# bqZUM_Scan_Shield.net
KiCad netlist of a schematic drawn in Altium Designer
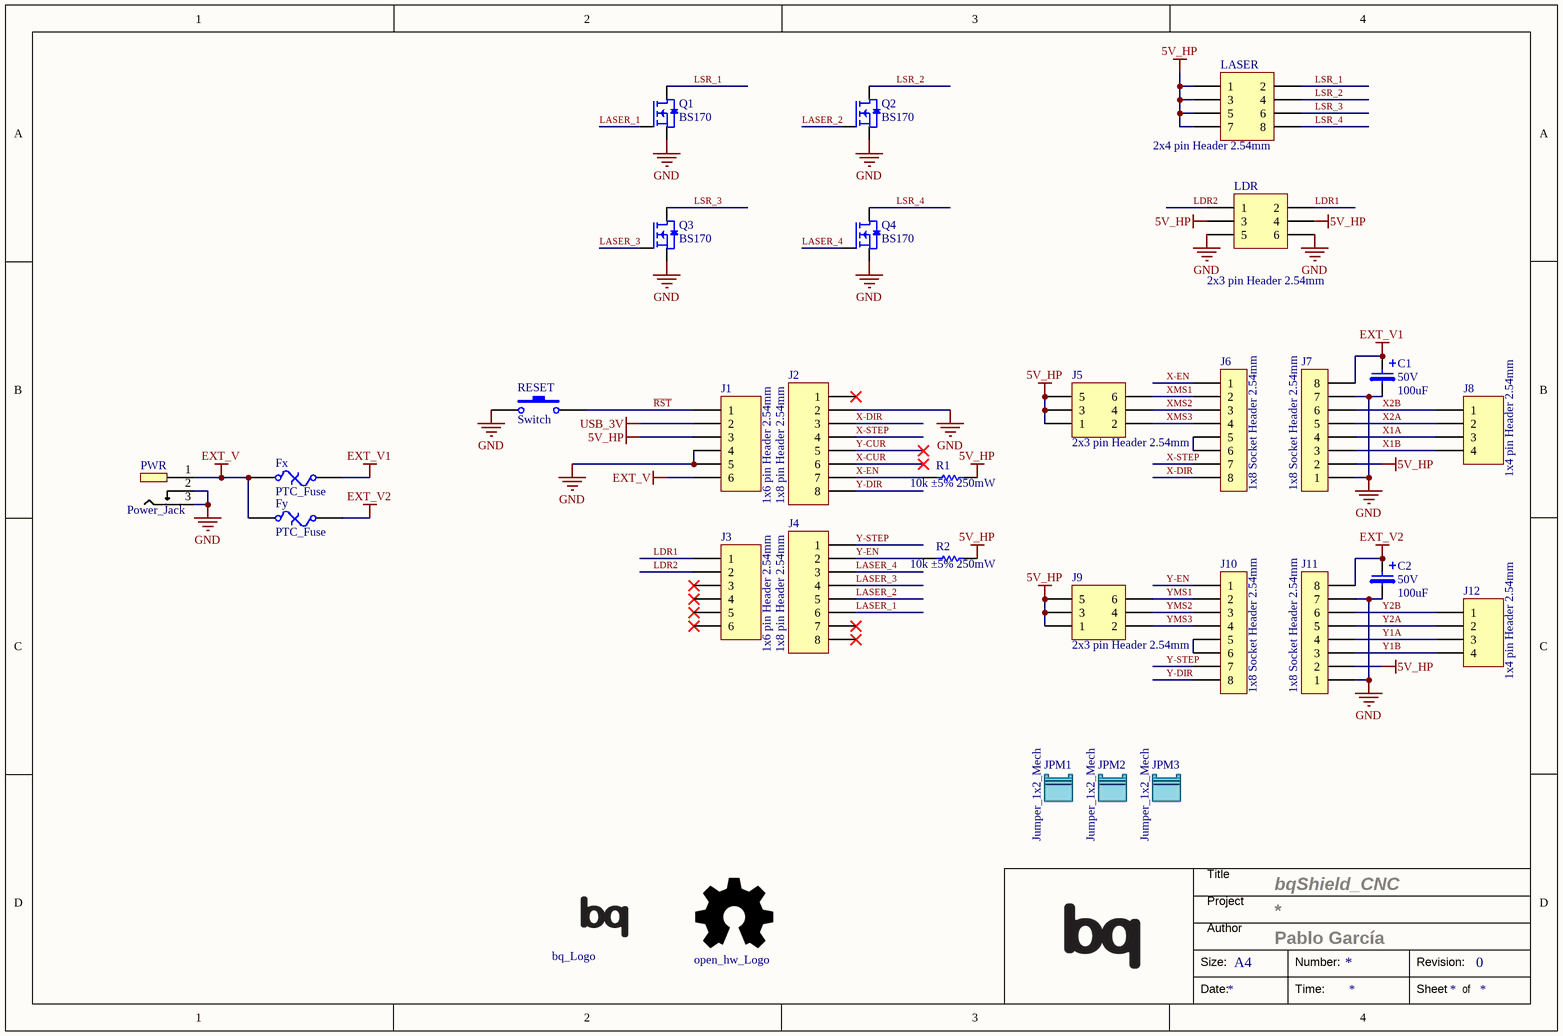
[diagram p0: bqZUM_Scan_Shield.SchDoc]

(export (version "E")
  (design (tool "Eeschema 10.0.6"))
  (components
    (comp (ref "C1")
      (value "Electrolytic")
      (footprint "Body_8-Height_11.5-Space_3,5_Folded")
      (description "Capacitor Electrolytic")
      (fields
        (field (name "VOLTAGE") "50V")
        (field (name "CAPACITANCE") "100uF")
        (field (name "PART NUMBER") "CAP_EL_100uF_50V")
        (field (name "MANUFACTURER") "Nichicon")
      )
      (libsource (lib "Pasives_Electrolytic_THT") (part "Electrolytic"))
    )
    (comp (ref "C2")
      (value "Electrolytic")
      (footprint "Body_8-Height_11.5-Space_3,5_Folded")
      (description "Capacitor Electrolytic")
      (fields
        (field (name "VOLTAGE") "50V")
        (field (name "CAPACITANCE") "100uF")
        (field (name "PART NUMBER") "CAP_EL_100uF_50V")
        (field (name "MANUFACTURER") "Nichicon")
      )
      (libsource (lib "Pasives_Electrolytic_THT") (part "Electrolytic"))
    )
    (comp (ref "Fx")
      (value "PTC_Fuse")
      (footprint "MF-Rxx_S1_12.0")
      (description "PTC Resettable Fuse")
      (fields (field (name "PART NUMBER") "FUSE 1.85A 30V") (field (name "VOLTAGE") "30V"))
      (libsource (lib "Protection") (part "PTC_Fuse"))
    )
    (comp (ref "Fy")
      (value "PTC_Fuse")
      (footprint "MF-Rxx_S1_12.0")
      (description "PTC Resettable Fuse")
      (fields (field (name "PART NUMBER") "FUSE 1.85A 30V") (field (name "VOLTAGE") "30V"))
      (libsource (lib "Protection") (part "PTC_Fuse"))
    )
    (comp (ref "J1")
      (value "1x6 pin Header 2.54mm")
      (footprint "1x6 Pin Header 2.54")
      (fields (field (name "MANUFACTURER") "Samtec") (field (name "PART NUMBER") "CON_PH_THT2.54_6"))
      (libsource (lib "Conectores_PinHeader_2.54") (part "1x6 pin Header 2.54mm"))
    )
    (comp (ref "J2")
      (value "1x8 pin Header 2.54mm")
      (footprint "1x8 Pin Header 2.54")
      (fields (field (name "MANUFACTURER") "Samtec") (field (name "PART NUMBER") "CON_PH_THT2.54_8"))
      (libsource (lib "Conectores_PinHeader_2.54") (part "1x8 pin Header 2.54mm"))
    )
    (comp (ref "J3")
      (value "1x6 pin Header 2.54mm")
      (footprint "1x6 Pin Header 2.54")
      (fields (field (name "MANUFACTURER") "Samtec") (field (name "PART NUMBER") "CON_PH_THT2.54_6"))
      (libsource (lib "Conectores_PinHeader_2.54") (part "1x6 pin Header 2.54mm"))
    )
    (comp (ref "J4")
      (value "1x8 pin Header 2.54mm")
      (footprint "1x8 Pin Header 2.54")
      (fields (field (name "MANUFACTURER") "Samtec") (field (name "PART NUMBER") "CON_PH_THT2.54_8"))
      (libsource (lib "Conectores_PinHeader_2.54") (part "1x8 pin Header 2.54mm"))
    )
    (comp (ref "J5")
      (value "2x3 pin Header 2.54mm")
      (footprint "2x3 Pin Header 2.54")
      (description "6 pin Dual Header 2.54mm")
      (fields (field (name "MANUFACTURER") "Samtec") (field (name "PART NUMBER") "CON_DPH_THT2.54_6"))
      (libsource (lib "Conectores_PinHeader_2.54") (part "2x3 pin Header 2.54mm"))
    )
    (comp (ref "J6")
      (value "1x8 Socket Header 2.54mm")
      (footprint "1x8 Socket Header THT 2.54mm")
      (description "8 pin Socket Header 2.54mm")
      (fields (field (name "MANUFACTURER") "Samtec") (field (name "PART NUMBER") "CON_SH_THT2.54_8"))
      (libsource (lib "") (part "1x8 Socket Header 2.54mm_1"))
    )
    (comp (ref "J7")
      (value "1x8 Socket Header 2.54mm")
      (footprint "1x8 Socket Header THT 2.54mm")
      (description "8 pin Socket Header 2.54mm")
      (fields (field (name "MANUFACTURER") "Samtec") (field (name "PART NUMBER") "CON_SH_THT2.54_8"))
      (libsource (lib "Conectores_SocketHeader_2.54") (part "1x8 Socket Header 2.54mm"))
    )
    (comp (ref "J8")
      (value "1x4 pin Header 2.54mm")
      (footprint "1x4 Pin Header 2.54")
      (fields (field (name "MANUFACTURER") "Samtec") (field (name "PART NUMBER") "CON_PH_THT2.54_4"))
      (libsource (lib "Conectores_PinHeader_2.54") (part "1x4 pin Header 2.54mm"))
    )
    (comp (ref "J9")
      (value "2x3 pin Header 2.54mm")
      (footprint "2x3 Pin Header 2.54")
      (description "6 pin Dual Header 2.54mm")
      (fields (field (name "MANUFACTURER") "Samtec") (field (name "PART NUMBER") "CON_DPH_THT2.54_6"))
      (libsource (lib "Conectores_PinHeader_2.54") (part "2x3 pin Header 2.54mm"))
    )
    (comp (ref "J10")
      (value "1x8 Socket Header 2.54mm")
      (footprint "1x8 Socket Header THT 2.54mm")
      (description "8 pin Socket Header 2.54mm")
      (fields (field (name "MANUFACTURER") "Samtec") (field (name "PART NUMBER") "CON_SH_THT2.54_8"))
      (libsource (lib "") (part "1x8 Socket Header 2.54mm_1"))
    )
    (comp (ref "J11")
      (value "1x8 Socket Header 2.54mm")
      (footprint "1x8 Socket Header THT 2.54mm")
      (description "8 pin Socket Header 2.54mm")
      (fields (field (name "MANUFACTURER") "Samtec") (field (name "PART NUMBER") "CON_SH_THT2.54_8"))
      (libsource (lib "Conectores_SocketHeader_2.54") (part "1x8 Socket Header 2.54mm"))
    )
    (comp (ref "J12")
      (value "1x4 pin Header 2.54mm")
      (footprint "1x4 Pin Header 2.54")
      (fields (field (name "MANUFACTURER") "Samtec") (field (name "PART NUMBER") "CON_PH_THT2.54_4"))
      (libsource (lib "Conectores_PinHeader_2.54") (part "1x4 pin Header 2.54mm"))
    )
    (comp (ref "JPM1")
      (value "Jumper_1x2_Mech")
      (description "1x2 Jumper 2.54mm")
      (fields (field (name "PART NUMBER") "Jumper_2pin_Mech") (field (name "MANUFACTURER") "Würth"))
      (libsource (lib "Connectors_Jumpers") (part "Jumper_1x2_Mech"))
    )
    (comp (ref "JPM2")
      (value "Jumper_1x2_Mech")
      (description "1x2 Jumper 2.54mm")
      (fields (field (name "PART NUMBER") "Jumper_2pin_Mech") (field (name "MANUFACTURER") "Würth"))
      (libsource (lib "Connectors_Jumpers") (part "Jumper_1x2_Mech"))
    )
    (comp (ref "JPM3")
      (value "Jumper_1x2_Mech")
      (description "1x2 Jumper 2.54mm")
      (fields (field (name "PART NUMBER") "Jumper_2pin_Mech") (field (name "MANUFACTURER") "Würth"))
      (libsource (lib "Connectors_Jumpers") (part "Jumper_1x2_Mech"))
    )
    (comp (ref "LASER")
      (value "2x4 pin Header 2.54mm")
      (footprint "2x4 Pin Header 2.54")
      (description "8 pin Dual Header 2.54mm")
      (fields (field (name "MANUFACTURER") "Samtec") (field (name "PART NUMBER") "CON_DPH_THT2.54_8"))
      (libsource (lib "Conectores_PinHeader_2.54") (part "2x4 pin Header 2.54mm"))
    )
    (comp (ref "LDR")
      (value "2x3 pin Header 2.54mm")
      (footprint "2x3 Pin Header 2.54")
      (description "6 pin Dual Header 2.54mm")
      (fields (field (name "MANUFACTURER") "Samtec") (field (name "PART NUMBER") "CON_DPH_THT2.54_6"))
      (libsource (lib "") (part "2x3 pin Header 2.54mm_1"))
    )
    (comp (ref "logo")
      (value "bq_Logo")
      (footprint "bq_Logo_small")
      (fields (field (name "PART NUMBER") "bq Logo Small"))
      (libsource (lib "Miscelanea") (part "bq_Logo"))
    )
    (comp (ref "openhw")
      (value "open_hw_Logo")
      (footprint "open_hw_Logo_small")
      (fields (field (name "PART NUMBER") "Open HW Logo Small"))
      (libsource (lib "Miscelanea") (part "open_hw_Logo"))
    )
    (comp (ref "PWR")
      (value "Power_Jack")
      (footprint "Jack 2.1")
      (description "DC Power Jack")
      (fields (field (name "MANUFACTURER") "Switchcraft"))
      (libsource (lib "Connectors_Power") (part "Power_Jack"))
    )
    (comp (ref "Q1")
      (value "BS170")
      (footprint "TO-92-3L")
      (description "Mosfet Channel N Enhancement Mode")
      (fields (field (name "MANUFACTURER") "Fairchild Semiconductor"))
      (libsource (lib "Semiconductors_Transistors") (part "Mosfet_N_TH"))
    )
    (comp (ref "Q2")
      (value "BS170")
      (footprint "TO-92-3L")
      (description "Mosfet Channel N Enhancement Mode")
      (fields (field (name "MANUFACTURER") "Fairchild Semiconductor"))
      (libsource (lib "Semiconductors_Transistors") (part "Mosfet_N_TH"))
    )
    (comp (ref "Q3")
      (value "BS170")
      (footprint "TO-92-3L")
      (description "Mosfet Channel N Enhancement Mode")
      (fields (field (name "MANUFACTURER") "Fairchild Semiconductor"))
      (libsource (lib "Semiconductors_Transistors") (part "Mosfet_N_TH"))
    )
    (comp (ref "Q4")
      (value "BS170")
      (footprint "TO-92-3L")
      (description "Mosfet Channel N Enhancement Mode")
      (fields (field (name "MANUFACTURER") "Fairchild Semiconductor"))
      (libsource (lib "Semiconductors_Transistors") (part "Mosfet_N_TH"))
    )
    (comp (ref "R1")
      (value "10k ±5% 250mW")
      (footprint "Resistor_THT_6mm")
      (description "Resistor")
      (fields (field (name "TOLERANCE") "±5%") (field (name "POWER") "250mW"))
      (libsource (lib "Pasives_Resistor_THT") (part "Resistor"))
    )
    (comp (ref "R2")
      (value "10k ±5% 250mW")
      (footprint "Resistor_THT_6mm")
      (description "Resistor")
      (fields (field (name "TOLERANCE") "±5%") (field (name "POWER") "250mW"))
      (libsource (lib "Pasives_Resistor_THT") (part "Resistor"))
    )
    (comp (ref "RESET")
      (value "Switch")
      (footprint "SW_THT_6.0x6.0x5.0")
      (description "Micro miniature pushbutton surface Switch")
      (fields (field (name "PART NUMBER") "SW THT 6x6x5") (field (name "MANUFACTURER") "Würth"))
      (libsource (lib "Electromechanical") (part "Switch"))
    )
  )
  (nets
    (net (code "1") (name "/LASER_1") (class "Default")
      (node (ref "J4") (pin "6") (pinfunction "6_6") (pintype "passive"))
      (node (ref "Q1") (pin "2") (pinfunction "G_2") (pintype "passive"))
    )
    (net (code "2") (name "/LASER_2") (class "Default")
      (node (ref "J4") (pin "5") (pinfunction "5_5") (pintype "passive"))
      (node (ref "Q2") (pin "2") (pinfunction "G_2") (pintype "passive"))
    )
    (net (code "3") (name "/LASER_3") (class "Default")
      (node (ref "J4") (pin "4") (pinfunction "4_4") (pintype "passive"))
      (node (ref "Q3") (pin "2") (pinfunction "G_2") (pintype "passive"))
    )
    (net (code "4") (name "/LASER_4") (class "Default")
      (node (ref "J4") (pin "3") (pinfunction "3_3") (pintype "passive"))
      (node (ref "Q4") (pin "2") (pinfunction "G_2") (pintype "passive"))
    )
    (net (code "5") (name "/LDR1") (class "Default")
      (node (ref "J3") (pin "1") (pinfunction "1_1") (pintype "passive"))
      (node (ref "LDR") (pin "2") (pinfunction "2_2") (pintype "passive"))
    )
    (net (code "6") (name "/LDR2") (class "Default")
      (node (ref "J3") (pin "2") (pinfunction "2_2") (pintype "passive"))
      (node (ref "LDR") (pin "1") (pinfunction "1_1") (pintype "passive"))
    )
    (net (code "7") (name "/LSR_1") (class "Default")
      (node (ref "LASER") (pin "2") (pinfunction "2_2") (pintype "passive"))
      (node (ref "Q1") (pin "3") (pinfunction "D_3") (pintype "passive"))
    )
    (net (code "8") (name "/LSR_2") (class "Default")
      (node (ref "LASER") (pin "4") (pinfunction "4_4") (pintype "passive"))
      (node (ref "Q2") (pin "3") (pinfunction "D_3") (pintype "passive"))
    )
    (net (code "9") (name "/LSR_3") (class "Default")
      (node (ref "LASER") (pin "6") (pinfunction "6_6") (pintype "passive"))
      (node (ref "Q3") (pin "3") (pinfunction "D_3") (pintype "passive"))
    )
    (net (code "10") (name "/LSR_4") (class "Default")
      (node (ref "LASER") (pin "8") (pinfunction "8_8") (pintype "passive"))
      (node (ref "Q4") (pin "3") (pinfunction "D_3") (pintype "passive"))
    )
    (net (code "11") (name "/X-CUR") (class "Default")
      (node (ref "J2") (pin "6") (pinfunction "6_6") (pintype "passive+no_connect"))
    )
    (net (code "12") (name "/X-DIR") (class "Default")
      (node (ref "J2") (pin "3") (pinfunction "3_3") (pintype "passive"))
      (node (ref "J6") (pin "8") (pinfunction "8_8") (pintype "passive"))
    )
    (net (code "13") (name "/X-EN") (class "Default")
      (node (ref "J2") (pin "7") (pinfunction "7_7") (pintype "passive"))
      (node (ref "J6") (pin "1") (pinfunction "1_1") (pintype "passive"))
      (node (ref "R1") (pin "1") (pinfunction "1_1") (pintype "passive"))
    )
    (net (code "14") (name "/X-STEP") (class "Default")
      (node (ref "J2") (pin "4") (pinfunction "4_4") (pintype "passive"))
      (node (ref "J6") (pin "7") (pinfunction "7_7") (pintype "passive"))
    )
    (net (code "15") (name "/X1A") (class "Default")
      (node (ref "J7") (pin "4") (pinfunction "4_4") (pintype "passive"))
      (node (ref "J8") (pin "3") (pinfunction "3_3") (pintype "passive"))
    )
    (net (code "16") (name "/X1B") (class "Default")
      (node (ref "J7") (pin "3") (pinfunction "3_3") (pintype "passive"))
      (node (ref "J8") (pin "4") (pinfunction "4_4") (pintype "passive"))
    )
    (net (code "17") (name "/X2A") (class "Default")
      (node (ref "J7") (pin "5") (pinfunction "5_5") (pintype "passive"))
      (node (ref "J8") (pin "2") (pinfunction "2_2") (pintype "passive"))
    )
    (net (code "18") (name "/X2B") (class "Default")
      (node (ref "J7") (pin "6") (pinfunction "6_6") (pintype "passive"))
      (node (ref "J8") (pin "1") (pinfunction "1_1") (pintype "passive"))
    )
    (net (code "19") (name "/XMS1") (class "Default")
      (node (ref "J5") (pin "6") (pinfunction "6_6") (pintype "passive"))
      (node (ref "J6") (pin "2") (pinfunction "2_2") (pintype "passive"))
    )
    (net (code "20") (name "/XMS2") (class "Default")
      (node (ref "J5") (pin "4") (pinfunction "4_4") (pintype "passive"))
      (node (ref "J6") (pin "3") (pinfunction "3_3") (pintype "passive"))
    )
    (net (code "21") (name "/XMS3") (class "Default")
      (node (ref "J5") (pin "2") (pinfunction "2_2") (pintype "passive"))
      (node (ref "J6") (pin "4") (pinfunction "4_4") (pintype "passive"))
    )
    (net (code "22") (name "/Y-CUR") (class "Default")
      (node (ref "J2") (pin "5") (pinfunction "5_5") (pintype "passive+no_connect"))
    )
    (net (code "23") (name "/Y-DIR") (class "Default")
      (node (ref "J10") (pin "8") (pinfunction "8_8") (pintype "passive"))
      (node (ref "J2") (pin "8") (pinfunction "8_8") (pintype "passive"))
    )
    (net (code "24") (name "/Y-EN") (class "Default")
      (node (ref "J10") (pin "1") (pinfunction "1_1") (pintype "passive"))
      (node (ref "J4") (pin "2") (pinfunction "2_2") (pintype "passive"))
      (node (ref "R2") (pin "1") (pinfunction "1_1") (pintype "passive"))
    )
    (net (code "25") (name "/Y-STEP") (class "Default")
      (node (ref "J10") (pin "7") (pinfunction "7_7") (pintype "passive"))
      (node (ref "J4") (pin "1") (pinfunction "1_1") (pintype "passive"))
    )
    (net (code "26") (name "/Y1A") (class "Default")
      (node (ref "J11") (pin "4") (pinfunction "4_4") (pintype "passive"))
      (node (ref "J12") (pin "3") (pinfunction "3_3") (pintype "passive"))
    )
    (net (code "27") (name "/Y1B") (class "Default")
      (node (ref "J11") (pin "3") (pinfunction "3_3") (pintype "passive"))
      (node (ref "J12") (pin "4") (pinfunction "4_4") (pintype "passive"))
    )
    (net (code "28") (name "/Y2A") (class "Default")
      (node (ref "J11") (pin "5") (pinfunction "5_5") (pintype "passive"))
      (node (ref "J12") (pin "2") (pinfunction "2_2") (pintype "passive"))
    )
    (net (code "29") (name "/Y2B") (class "Default")
      (node (ref "J11") (pin "6") (pinfunction "6_6") (pintype "passive"))
      (node (ref "J12") (pin "1") (pinfunction "1_1") (pintype "passive"))
    )
    (net (code "30") (name "/YMS1") (class "Default")
      (node (ref "J10") (pin "2") (pinfunction "2_2") (pintype "passive"))
      (node (ref "J9") (pin "6") (pinfunction "6_6") (pintype "passive"))
    )
    (net (code "31") (name "/YMS2") (class "Default")
      (node (ref "J10") (pin "3") (pinfunction "3_3") (pintype "passive"))
      (node (ref "J9") (pin "4") (pinfunction "4_4") (pintype "passive"))
    )
    (net (code "32") (name "/YMS3") (class "Default")
      (node (ref "J10") (pin "4") (pinfunction "4_4") (pintype "passive"))
      (node (ref "J9") (pin "2") (pinfunction "2_2") (pintype "passive"))
    )
    (net (code "33") (name "/~{RST}") (class "Default")
      (node (ref "J1") (pin "1") (pinfunction "1_1") (pintype "passive"))
      (node (ref "RESET") (pin "2") (pinfunction "2_2") (pintype "passive"))
    )
    (net (code "34") (name "5V_HP") (class "Default")
      (node (ref "J1") (pin "3") (pinfunction "3_3") (pintype "passive"))
      (node (ref "J11") (pin "2") (pinfunction "2_2") (pintype "passive"))
      (node (ref "J5") (pin "1") (pinfunction "1_1") (pintype "passive"))
      (node (ref "J5") (pin "3") (pinfunction "3_3") (pintype "passive"))
      (node (ref "J5") (pin "5") (pinfunction "5_5") (pintype "passive"))
      (node (ref "J7") (pin "2") (pinfunction "2_2") (pintype "passive"))
      (node (ref "J9") (pin "1") (pinfunction "1_1") (pintype "passive"))
      (node (ref "J9") (pin "3") (pinfunction "3_3") (pintype "passive"))
      (node (ref "J9") (pin "5") (pinfunction "5_5") (pintype "passive"))
      (node (ref "LASER") (pin "1") (pinfunction "1_1") (pintype "passive"))
      (node (ref "LASER") (pin "3") (pinfunction "3_3") (pintype "passive"))
      (node (ref "LASER") (pin "5") (pinfunction "5_5") (pintype "passive"))
      (node (ref "LASER") (pin "7") (pinfunction "7_7") (pintype "passive"))
      (node (ref "LDR") (pin "3") (pinfunction "3_3") (pintype "passive"))
      (node (ref "LDR") (pin "4") (pinfunction "4_4") (pintype "passive"))
      (node (ref "R1") (pin "2") (pinfunction "2_2") (pintype "passive"))
      (node (ref "R2") (pin "2") (pinfunction "2_2") (pintype "passive"))
    )
    (net (code "35") (name "EXT_V") (class "Default")
      (node (ref "Fx") (pin "1") (pinfunction "1_1") (pintype "passive"))
      (node (ref "Fy") (pin "1") (pinfunction "1_1") (pintype "passive"))
      (node (ref "J1") (pin "6") (pinfunction "6_6") (pintype "passive"))
      (node (ref "PWR") (pin "1") (pinfunction "1_1") (pintype "passive"))
    )
    (net (code "36") (name "EXT_V1") (class "Default")
      (node (ref "C1") (pin "1") (pinfunction "1_1") (pintype "passive"))
      (node (ref "Fx") (pin "2") (pinfunction "2_2") (pintype "passive"))
      (node (ref "J7") (pin "8") (pinfunction "8_8") (pintype "passive"))
    )
    (net (code "37") (name "EXT_V2") (class "Default")
      (node (ref "C2") (pin "1") (pinfunction "1_1") (pintype "passive"))
      (node (ref "Fy") (pin "2") (pinfunction "2_2") (pintype "passive"))
      (node (ref "J11") (pin "8") (pinfunction "8_8") (pintype "passive"))
    )
    (net (code "38") (name "GND") (class "Default")
      (node (ref "C1") (pin "2") (pinfunction "2_2") (pintype "passive"))
      (node (ref "C2") (pin "2") (pinfunction "2_2") (pintype "passive"))
      (node (ref "J1") (pin "4") (pinfunction "4_4") (pintype "passive"))
      (node (ref "J1") (pin "5") (pinfunction "5_5") (pintype "passive"))
      (node (ref "J11") (pin "1") (pinfunction "1_1") (pintype "passive"))
      (node (ref "J11") (pin "7") (pinfunction "7_7") (pintype "passive"))
      (node (ref "J2") (pin "2") (pinfunction "2_2") (pintype "passive"))
      (node (ref "J7") (pin "1") (pinfunction "1_1") (pintype "passive"))
      (node (ref "J7") (pin "7") (pinfunction "7_7") (pintype "passive"))
      (node (ref "LDR") (pin "5") (pinfunction "5_5") (pintype "passive"))
      (node (ref "LDR") (pin "6") (pinfunction "6_6") (pintype "passive"))
      (node (ref "PWR") (pin "2") (pinfunction "2_2") (pintype "passive"))
      (node (ref "PWR") (pin "3") (pinfunction "3_3") (pintype "passive"))
      (node (ref "Q1") (pin "1") (pinfunction "S_1") (pintype "passive"))
      (node (ref "Q2") (pin "1") (pinfunction "S_1") (pintype "passive"))
      (node (ref "Q3") (pin "1") (pinfunction "S_1") (pintype "passive"))
      (node (ref "Q4") (pin "1") (pinfunction "S_1") (pintype "passive"))
      (node (ref "RESET") (pin "1") (pinfunction "1_1") (pintype "passive"))
    )
    (net (code "39") (name "Net-(J6-Pad5)") (class "Default")
      (node (ref "J6") (pin "5") (pinfunction "5_5") (pintype "passive"))
      (node (ref "J6") (pin "6") (pinfunction "6_6") (pintype "passive"))
    )
    (net (code "40") (name "Net-(J10-Pad5)") (class "Default")
      (node (ref "J10") (pin "5") (pinfunction "5_5") (pintype "passive"))
      (node (ref "J10") (pin "6") (pinfunction "6_6") (pintype "passive"))
    )
    (net (code "41") (name "USB_3V") (class "Default")
      (node (ref "J1") (pin "2") (pinfunction "2_2") (pintype "passive"))
    )
    (net (code "42") (name "unconnected-(J2-Pad1)") (class "Default")
      (node (ref "J2") (pin "1") (pinfunction "1_1") (pintype "passive+no_connect"))
    )
    (net (code "43") (name "unconnected-(J3-Pad3)") (class "Default")
      (node (ref "J3") (pin "3") (pinfunction "3_3") (pintype "passive+no_connect"))
    )
    (net (code "44") (name "unconnected-(J3-Pad4)") (class "Default")
      (node (ref "J3") (pin "4") (pinfunction "4_4") (pintype "passive+no_connect"))
    )
    (net (code "45") (name "unconnected-(J3-Pad5)") (class "Default")
      (node (ref "J3") (pin "5") (pinfunction "5_5") (pintype "passive+no_connect"))
    )
    (net (code "46") (name "unconnected-(J3-Pad6)") (class "Default")
      (node (ref "J3") (pin "6") (pinfunction "6_6") (pintype "passive+no_connect"))
    )
    (net (code "47") (name "unconnected-(J4-Pad7)") (class "Default")
      (node (ref "J4") (pin "7") (pinfunction "7_7") (pintype "passive+no_connect"))
    )
    (net (code "48") (name "unconnected-(J4-Pad8)") (class "Default")
      (node (ref "J4") (pin "8") (pinfunction "8_8") (pintype "passive+no_connect"))
    )
  )
)
